# Trottinette_Telemetrie_Circuit.net
KiCad netlist of a schematic drawn in Altium Designer
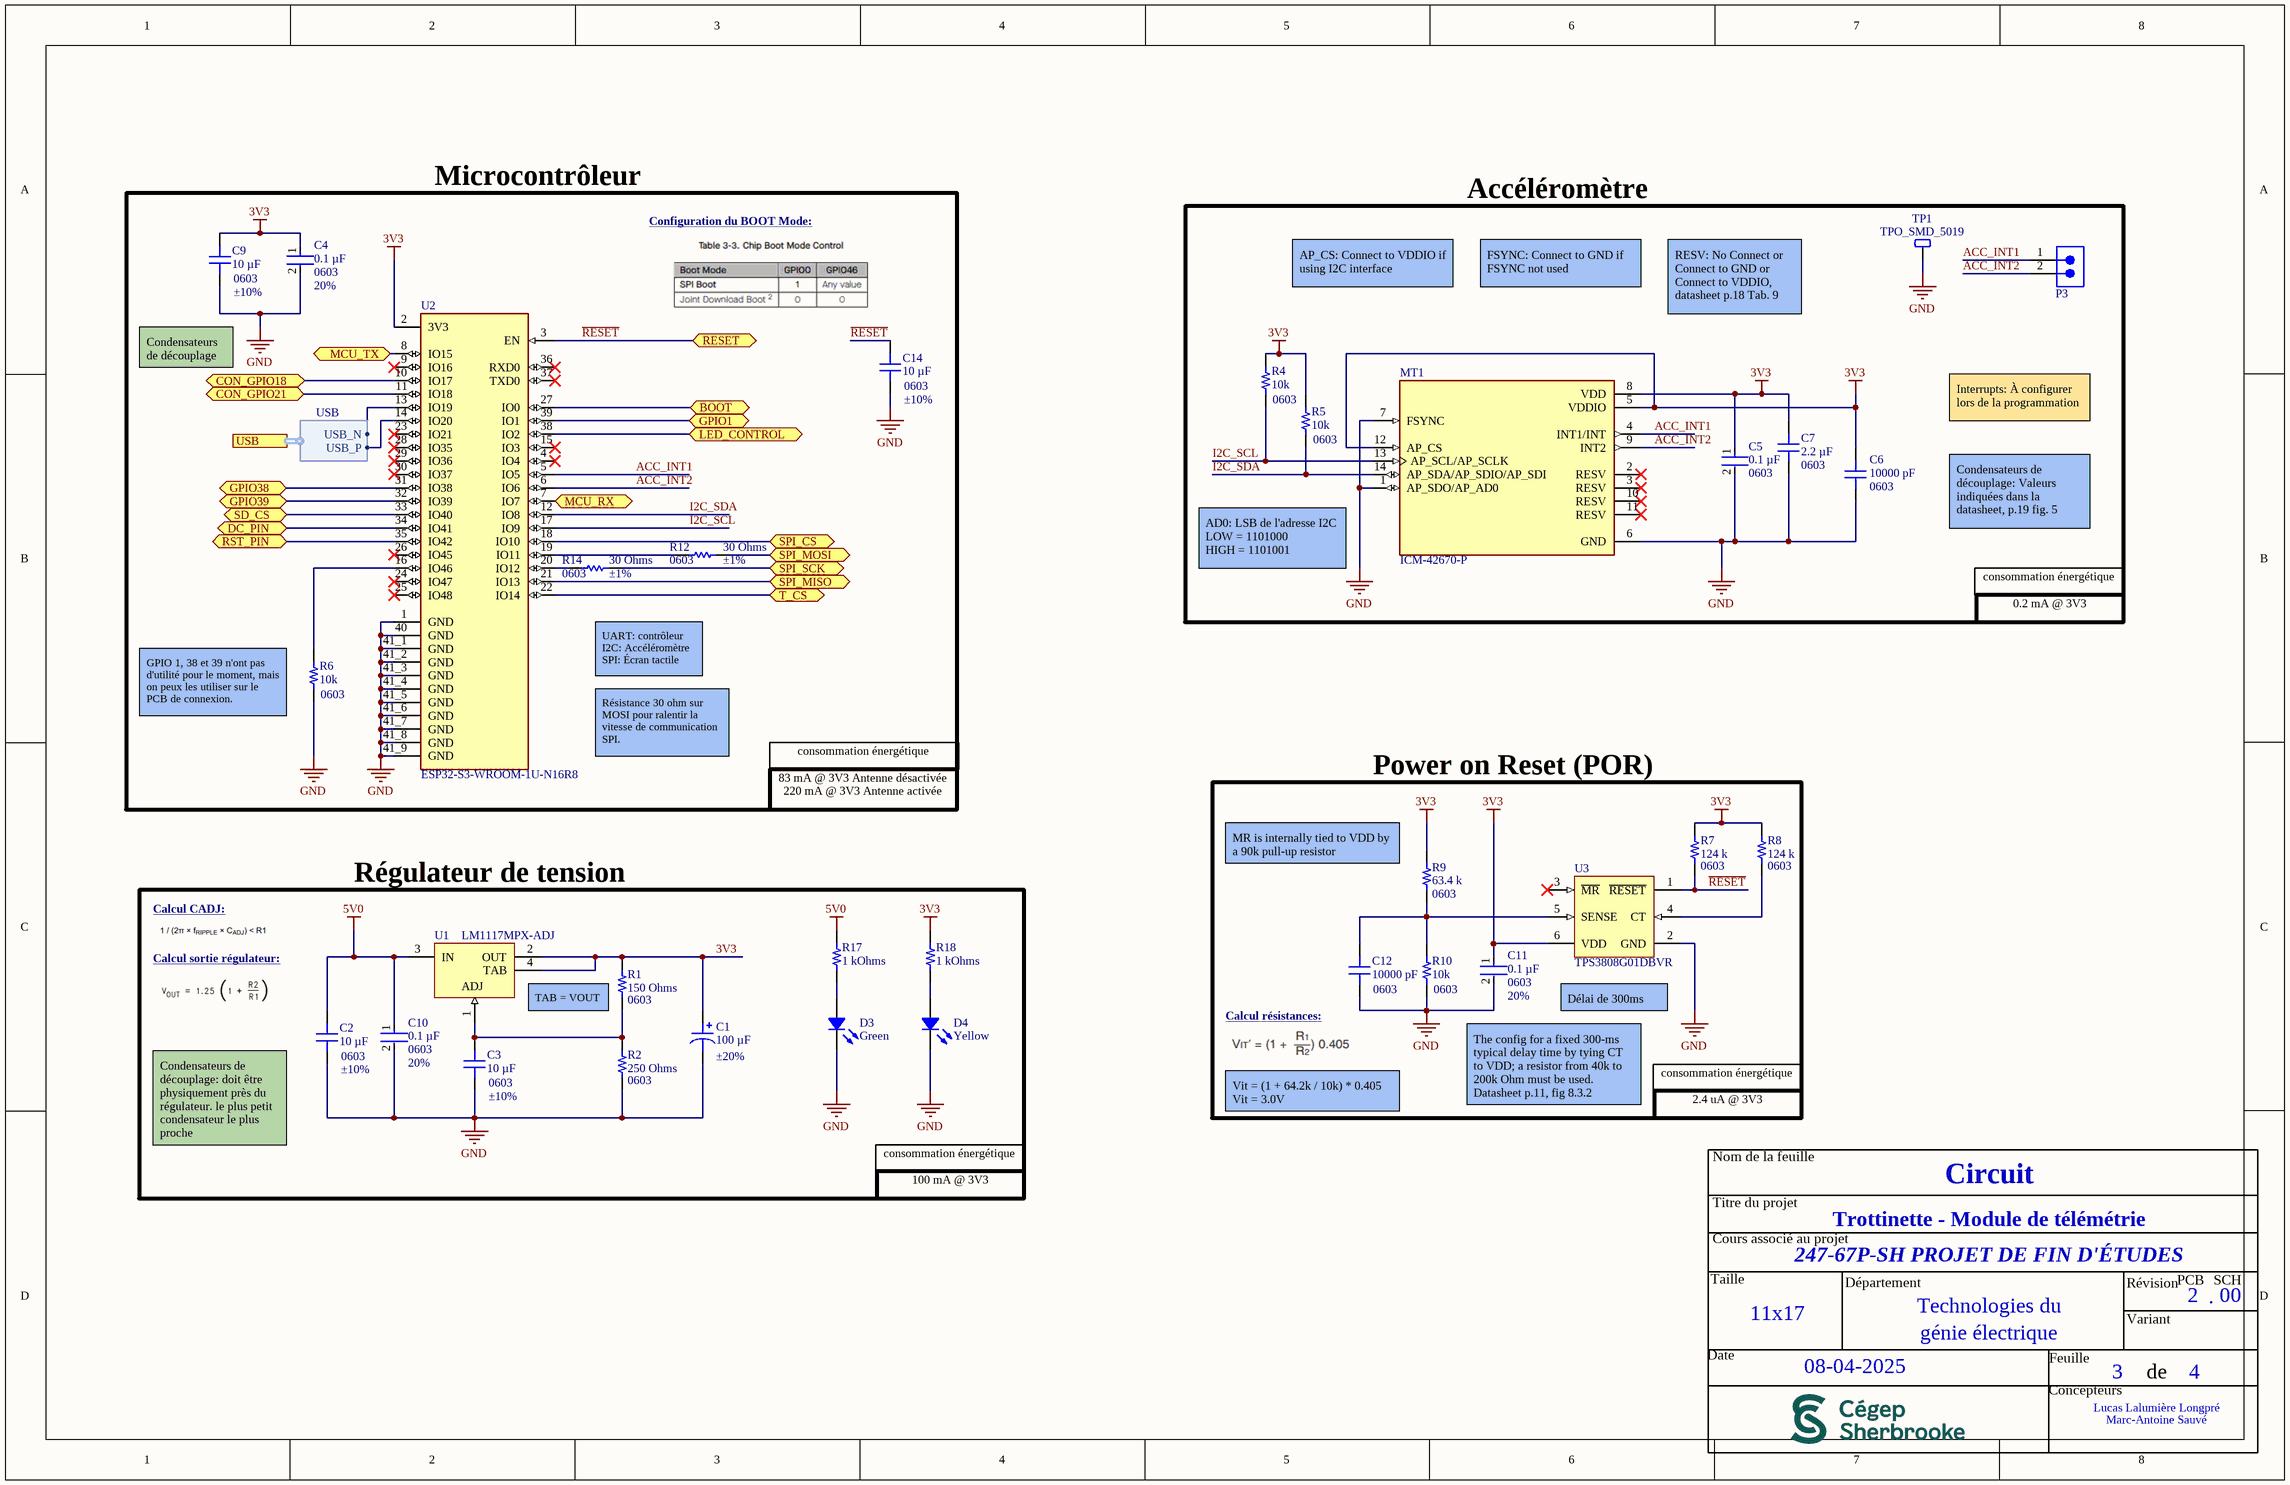
[diagram p0: Trottinette_Telemetrie_Circuit.SchDoc]

(export (version "E")
  (design (tool "Eeschema 10.0.6"))
  (components
    (comp (ref "C1")
      (value "100 µF")
      (footprint "CAP ALSMD 6.6MM H6.1MM")
      (description "CAP ALUM 100UF 20% 10V SMD")
      (fields
        (field (name "PART NUMBER") "10SGV100M6.3X6.1")
        (field (name "MANUFACTURER") "Rubycon")
        (field (name "TOLERANCE") "±20%")
      )
      (libsource (lib "Celestial Altium Library - altium_library") (part "Polarised Capacitor"))
    )
    (comp (ref "C2")
      (value "10 µF")
      (footprint "CAP 0603_1608")
      (description "CAP CER 10UF 10V X5R 0603")
      (fields
        (field (name "PART NUMBER") "GRT188R61A106KE13D")
        (field (name "DEVICE PACKAGE") "0603")
        (field (name "MANUFACTURER") "Murata Electronics")
        (field (name "TOLERANCE") "±10%")
      )
      (libsource (lib "Celestial Altium Library - altium_library") (part "Capacitor"))
    )
    (comp (ref "C3")
      (value "10 µF")
      (footprint "CAP 0603_1608")
      (description "CAP CER 10UF 10V X5R 0603")
      (fields
        (field (name "PART NUMBER") "GRT188R61A106KE13D")
        (field (name "DEVICE PACKAGE") "0603")
        (field (name "MANUFACTURER") "Murata Electronics")
        (field (name "TOLERANCE") "±10%")
      )
      (libsource (lib "Celestial Altium Library - altium_library") (part "Capacitor"))
    )
    (comp (ref "C4")
      (value "0603ZC104MAT2A")
      (footprint "FP-0603-L_1_6_0_15-W_0_81-IPC_B")
      (description "General Purpose Ceramic Capacitor, 0603, 100nF, 20%, X7R, 15%, 10V")
      (fields
        (field (name "CASE CODE (IMPERIAL)") "0603")
        (field (name "TOLERANCE") "20%")
        (field (name "CAPACITANCE") "0.1 µF")
      )
      (libsource (lib "Altium Content Vault") (part "02cd4be3c70576c341d710602a673aa"))
    )
    (comp (ref "C5")
      (value "0603ZC104MAT2A")
      (footprint "FP-0603-L_1_6_0_15-W_0_81-IPC_B")
      (description "General Purpose Ceramic Capacitor, 0603, 100nF, 20%, X7R, 15%, 10V")
      (fields
        (field (name "CASE CODE (IMPERIAL)") "0603")
        (field (name "TOLERANCE") "20%")
        (field (name "CAPACITANCE") "0.1 µF")
      )
      (libsource (lib "Altium Content Vault") (part "02cd4be3c70576c341d710602a673aa"))
    )
    (comp (ref "C6")
      (value "10000 pF")
      (footprint "CAP 0603_1608")
      (description "CAP CER 0603 10NF 16V X7R 10%")
      (fields
        (field (name "PART NUMBER") "C0603C103K4RECAUTO")
        (field (name "MANUFACTURER") "KEMET")
        (field (name "PACKAGE / CASE") "0603")
      )
      (libsource (lib "Celestial Altium Library - altium_library") (part "Capacitor"))
    )
    (comp (ref "C7")
      (value "2.2 µF")
      (footprint "CAP 0603_1608")
      (description "CAP CER 2.2UF 16V Y5V 0603")
      (fields
        (field (name "PART NUMBER") "CC0603ZRY5V7BB225")
        (field (name "MANUFACTURER") "Yageo")
        (field (name "PACKAGE / CASE") "0603")
      )
      (libsource (lib "Celestial Altium Library - altium_library") (part "Capacitor"))
    )
    (comp (ref "C9")
      (value "10 µF")
      (footprint "CAP 0603_1608")
      (description "CAP CER 10UF 10V X5R 0603")
      (fields
        (field (name "PART NUMBER") "GRT188R61A106KE13D")
        (field (name "DEVICE PACKAGE") "0603")
        (field (name "MANUFACTURER") "Murata Electronics")
        (field (name "TOLERANCE") "±10%")
      )
      (libsource (lib "Celestial Altium Library - altium_library") (part "Capacitor"))
    )
    (comp (ref "C10")
      (value "0603ZC104MAT2A")
      (footprint "FP-0603-L_1_6_0_15-W_0_81-IPC_B")
      (description "General Purpose Ceramic Capacitor, 0603, 100nF, 20%, X7R, 15%, 10V")
      (fields
        (field (name "CASE CODE (IMPERIAL)") "0603")
        (field (name "TOLERANCE") "20%")
        (field (name "CAPACITANCE") "0.1 µF")
      )
      (libsource (lib "Altium Content Vault") (part "02cd4be3c70576c341d710602a673aa"))
    )
    (comp (ref "C11")
      (value "0603ZC104MAT2A")
      (footprint "FP-0603-L_1_6_0_15-W_0_81-IPC_B")
      (description "General Purpose Ceramic Capacitor, 0603, 100nF, 20%, X7R, 15%, 10V")
      (fields
        (field (name "CASE CODE (IMPERIAL)") "0603")
        (field (name "TOLERANCE") "20%")
        (field (name "CAPACITANCE") "0.1 µF")
      )
      (libsource (lib "Altium Content Vault") (part "02cd4be3c70576c341d710602a673aa"))
    )
    (comp (ref "C12")
      (value "10000 pF")
      (footprint "CAP 0603_1608")
      (description "CAP CER 10000PF 100V X7R 0603")
      (fields
        (field (name "PART NUMBER") "AC0603KRX7R0BB103")
        (field (name "DEVICE PACKAGE") "0603")
        (field (name "MANUFACTURER") "Yageo")
      )
      (libsource (lib "Celestial Altium Library - altium_library") (part "Capacitor"))
    )
    (comp (ref "C14")
      (value "10 µF")
      (footprint "CAP 0603_1608")
      (description "CAP CER 10UF 10V X5R 0603")
      (fields
        (field (name "PART NUMBER") "GRT188R61A106KE13D")
        (field (name "DEVICE PACKAGE") "0603")
        (field (name "MANUFACTURER") "Murata Electronics")
        (field (name "TOLERANCE") "±10%")
      )
      (libsource (lib "Celestial Altium Library - altium_library") (part "Capacitor"))
    )
    (comp (ref "D3")
      (value "Green")
      (footprint "LED 0603_1608 GREEN")
      (description "LED GREEN 0603 SMD")
      (fields (field (name "PART NUMBER") "5973316507F") (field (name "MANUFACTURER") "Dialight"))
      (libsource (lib "Celestial Altium Library - altium_library") (part "LED"))
    )
    (comp (ref "D4")
      (value "Yellow")
      (footprint "LED 0603_1608 YELLOW")
      (description "LED YELLOW 0603 SMD")
      (fields (field (name "PART NUMBER") "5990040007F") (field (name "MANUFACTURER") "Dialight"))
      (libsource (lib "Celestial Altium Library - altium_library") (part "LED"))
    )
    (comp (ref "MT1")
      (value "ICM-42670-P")
      (footprint "XDCR_ICM-42670-P")
      (libsource (lib "ICM-42670-P") (part "ICM-42670-P"))
    )
    (comp (ref "P3")
      (value "61300211121")
      (footprint "61300211121")
      (description "WR-PHD Pin Header, THT, Vertical, pitch 2.54mm, 1 Row, 2P")
      (fields (field (name "MANUFACTURER") "Wurth Elektronik"))
      (libsource (lib "Altium_WR-PHD_rev24a") (part "61300211121"))
    )
    (comp (ref "R1")
      (value "150 Ohms")
      (footprint "RES 0603_1608")
      (description "RES 150 OHM 1% 1/10W 0603")
      (fields
        (field (name "PART NUMBER") "RMCF0603FT150R")
        (field (name "MANUFACTURER") "Stackpole Electronics Inc")
        (field (name "SUPPLIER DEVICE PACKAGE") "0603")
      )
      (libsource (lib "Celestial Altium Library - altium_library") (part "Resistor"))
    )
    (comp (ref "R2")
      (value "250 Ohms")
      (footprint "RES 0603_1608")
      (description "RES 250 OHM 5% 1/8W 0603")
      (fields
        (field (name "PART NUMBER") "CH0603-250RJNTA")
        (field (name "MANUFACTURER") "Vishay Sfernice")
        (field (name "SUPPLIER DEVICE PACKAGE") "0603")
      )
      (libsource (lib "Celestial Altium Library - altium_library") (part "Resistor"))
    )
    (comp (ref "R4")
      (value "10k")
      (footprint "RES 0603_1608")
      (description "RES 10K OHM 0.1% 1/16W 0603")
      (fields
        (field (name "PART NUMBER") "RNCS0603BKE10K0")
        (field (name "MANUFACTURER") "Stackpole Electronics Inc")
        (field (name "SUPPLIER DEVICE PACKAGE") "0603")
      )
      (libsource (lib "Celestial Altium Library - altium_library") (part "Resistor"))
    )
    (comp (ref "R5")
      (value "10k")
      (footprint "RES 0603_1608")
      (description "RES 10K OHM 0.1% 1/16W 0603")
      (fields
        (field (name "PART NUMBER") "RNCS0603BKE10K0")
        (field (name "MANUFACTURER") "Stackpole Electronics Inc")
        (field (name "SUPPLIER DEVICE PACKAGE") "0603")
      )
      (libsource (lib "Celestial Altium Library - altium_library") (part "Resistor"))
    )
    (comp (ref "R6")
      (value "10k")
      (footprint "RES 0603_1608")
      (description "RES 10K OHM 0.1% 1/16W 0603")
      (fields
        (field (name "PART NUMBER") "RNCS0603BKE10K0")
        (field (name "MANUFACTURER") "Stackpole Electronics Inc")
        (field (name "SUPPLIER DEVICE PACKAGE") "0603")
      )
      (libsource (lib "Celestial Altium Library - altium_library") (part "Resistor"))
    )
    (comp (ref "R7")
      (value "124 k")
      (footprint "RES 0603_1608")
      (description "RES 124K OHM 1% 1/10W 0603")
      (fields
        (field (name "PART NUMBER") "RMCF0603FT124K")
        (field (name "MANUFACTURER") "Stackpole Electronics Inc")
        (field (name "SUPPLIER DEVICE PACKAGE") "0603")
      )
      (libsource (lib "Celestial Altium Library - altium_library") (part "Resistor"))
    )
    (comp (ref "R8")
      (value "124 k")
      (footprint "RES 0603_1608")
      (description "RES 124K OHM 1% 1/10W 0603")
      (fields
        (field (name "PART NUMBER") "RMCF0603FT124K")
        (field (name "MANUFACTURER") "Stackpole Electronics Inc")
        (field (name "SUPPLIER DEVICE PACKAGE") "0603")
      )
      (libsource (lib "Celestial Altium Library - altium_library") (part "Resistor"))
    )
    (comp (ref "R9")
      (value "63.4 k")
      (footprint "RES 0603_1608")
      (description "RES 63.4K OHM 1% 1/10W 0603")
      (fields
        (field (name "PART NUMBER") "RMCF0603FT63K4")
        (field (name "MANUFACTURER") "Stackpole Electronics Inc")
        (field (name "SUPPLIER DEVICE PACKAGE") "0603")
      )
      (libsource (lib "Celestial Altium Library - altium_library") (part "Resistor"))
    )
    (comp (ref "R10")
      (value "10k")
      (footprint "RES 0603_1608")
      (description "RES 10K OHM 0.1% 1/16W 0603")
      (fields
        (field (name "PART NUMBER") "RNCS0603BKE10K0")
        (field (name "MANUFACTURER") "Stackpole Electronics Inc")
        (field (name "SUPPLIER DEVICE PACKAGE") "0603")
      )
      (libsource (lib "Celestial Altium Library - altium_library") (part "Resistor"))
    )
    (comp (ref "R12")
      (value "ERJ3EKF30R0V")
      (footprint "RESC1608X55X30LL15T15")
      (fields (field (name "MANUFACTURER") "Panasonic"))
      (libsource (lib "Altium Content Vault") (part "RES"))
    )
    (comp (ref "R14")
      (value "ERJ3EKF30R0V")
      (footprint "RESC1608X55X30LL15T15")
      (fields (field (name "MANUFACTURER") "Panasonic"))
      (libsource (lib "Altium Content Vault") (part "RES"))
    )
    (comp (ref "R17")
      (value "1 kOhms")
      (footprint "RES 0603_1608")
      (description "RES SMD 1K OHM 0.1% 1/16W 0603")
      (fields
        (field (name "PART NUMBER") "CPF0603B1K0E")
        (field (name "MANUFACTURER") "TE Connectivity Passive Product")
      )
      (libsource (lib "Celestial Altium Library - altium_library") (part "Resistor"))
    )
    (comp (ref "R18")
      (value "1 kOhms")
      (footprint "RES 0603_1608")
      (description "RES SMD 1K OHM 0.1% 1/16W 0603")
      (fields
        (field (name "PART NUMBER") "CPF0603B1K0E")
        (field (name "MANUFACTURER") "TE Connectivity Passive Product")
      )
      (libsource (lib "Celestial Altium Library - altium_library") (part "Resistor"))
    )
    (comp (ref "TP1")
      (value "TPO_SMD_5019")
      (footprint "TPO_SMD_5019")
      (description "TPO - PC TEST POINT MINI - SMD")
      (fields (field (name "SOURCE") "CEGEP_SHERBROOKE_TGE_LIBRARY.SchLib"))
      (libsource (lib "Cegep de Sherbrooke") (part "TPO_SMD_5019"))
    )
    (comp (ref "U1")
      (value "LM1117MPX-ADJ")
      (footprint "MP04A_N")
      (description "800mA Low-Dropout Linear Regulator, 4-pin SOT-223")
      (fields (field (name "MANUFACTURER") "National Semiconductor"))
      (libsource (lib "Altium Content Vault") (part "PM-REG-LM1086ADJ-SOT4"))
    )
    (comp (ref "U2")
      (value "ESP32-S3-WROOM-1U-N16R8")
      (footprint "XCVR_ESP32-S3-WROOM-1U-N16R8")
      (fields (field (name "MF") "Espressif Systems"))
      (libsource (lib "ESP32-S3-WROOM-1U-N16R8") (part "ESP32-S3-WROOM-1U-N16R8"))
    )
    (comp (ref "U3")
      (value "TPS3808G01DBVR")
      (footprint "DBV0006A_L")
      (fields (field (name "MANUFACTURER") "Texas Instruments"))
      (libsource (lib "Altium Content Vault") (part "TI-TPS3808G01DBV6"))
    )
  )
  (nets
    (net (code "2") (name "/ACC_INT1") (class "Default")
      (node (ref "MT1") (pin "4") (pinfunction "INT1/INT_4") (pintype "output"))
      (node (ref "P3") (pin "1") (pinfunction "1_1") (pintype "passive"))
      (node (ref "U2") (pin "5") (pinfunction "IO5_5") (pintype "bidirectional"))
    )
    (net (code "3") (name "/ACC_INT2") (class "Default")
      (node (ref "MT1") (pin "9") (pinfunction "INT2_9") (pintype "output"))
      (node (ref "P3") (pin "2") (pinfunction "2_2") (pintype "passive"))
      (node (ref "U2") (pin "6") (pinfunction "IO6_6") (pintype "bidirectional"))
    )
    (net (code "4") (name "/BOOT") (class "Default")
      (node (ref "U2") (pin "27") (pinfunction "IO0_27") (pintype "bidirectional"))
    )
    (net (code "5") (name "/CON_GPIO18") (class "Default")
      (node (ref "U2") (pin "10") (pinfunction "IO17_10") (pintype "bidirectional"))
    )
    (net (code "6") (name "/CON_GPIO21") (class "Default")
      (node (ref "U2") (pin "11") (pinfunction "IO18_11") (pintype "bidirectional"))
    )
    (net (code "7") (name "/DC_PIN") (class "Default")
      (node (ref "U2") (pin "34") (pinfunction "IO41_34") (pintype "bidirectional"))
    )
    (net (code "8") (name "/GPIO1") (class "Default")
      (node (ref "U2") (pin "39") (pinfunction "IO1_39") (pintype "bidirectional"))
    )
    (net (code "9") (name "/GPIO38") (class "Default")
      (node (ref "U2") (pin "31") (pinfunction "IO38_31") (pintype "bidirectional"))
    )
    (net (code "10") (name "/GPIO39") (class "Default")
      (node (ref "U2") (pin "32") (pinfunction "IO39_32") (pintype "bidirectional"))
    )
    (net (code "11") (name "/I2C_SCL") (class "Default")
      (node (ref "MT1") (pin "13") (pinfunction "AP_SCL/AP_SCLK_13") (pintype "input"))
      (node (ref "R4") (pin "1") (pinfunction "1_1") (pintype "passive"))
      (node (ref "U2") (pin "17") (pinfunction "IO9_17") (pintype "bidirectional"))
    )
    (net (code "12") (name "/I2C_SDA") (class "Default")
      (node (ref "MT1") (pin "14") (pinfunction "AP_SDA/AP_SDIO/AP_SDI_14") (pintype "bidirectional"))
      (node (ref "R5") (pin "1") (pinfunction "1_1") (pintype "passive"))
      (node (ref "U2") (pin "12") (pinfunction "IO8_12") (pintype "bidirectional"))
    )
    (net (code "13") (name "/LED_CONTROL") (class "Default")
      (node (ref "U2") (pin "38") (pinfunction "IO2_38") (pintype "bidirectional"))
    )
    (net (code "14") (name "/MCU_RX") (class "Default")
      (node (ref "U2") (pin "7") (pinfunction "IO7_7") (pintype "bidirectional"))
    )
    (net (code "15") (name "/MCU_TX") (class "Default")
      (node (ref "U2") (pin "8") (pinfunction "IO15_8") (pintype "bidirectional"))
    )
    (net (code "16") (name "/RESET") (class "Default")
      (node (ref "C14") (pin "2") (pinfunction "2_2") (pintype "passive"))
      (node (ref "R7") (pin "1") (pinfunction "1_1") (pintype "passive"))
      (node (ref "U2") (pin "3") (pinfunction "EN_3") (pintype "input"))
      (node (ref "U3") (pin "1") (pinfunction "~{RESET}_1") (pintype "tri_state"))
    )
    (net (code "17") (name "/RST_PIN") (class "Default")
      (node (ref "U2") (pin "35") (pinfunction "IO42_35") (pintype "bidirectional"))
    )
    (net (code "18") (name "/SD_CS") (class "Default")
      (node (ref "U2") (pin "33") (pinfunction "IO40_33") (pintype "bidirectional"))
    )
    (net (code "19") (name "/SPI_CS") (class "Default")
      (node (ref "U2") (pin "18") (pinfunction "IO10_18") (pintype "bidirectional"))
    )
    (net (code "20") (name "/SPI_MISO") (class "Default")
      (node (ref "U2") (pin "21") (pinfunction "IO13_21") (pintype "bidirectional"))
    )
    (net (code "21") (name "/SPI_MOSI") (class "Default")
      (node (ref "R12") (pin "2") (pinfunction "2_2") (pintype "passive"))
    )
    (net (code "22") (name "/SPI_SCK") (class "Default")
      (node (ref "R14") (pin "2") (pinfunction "2_2") (pintype "passive"))
    )
    (net (code "23") (name "/T_CS") (class "Default")
      (node (ref "U2") (pin "22") (pinfunction "IO14_22") (pintype "bidirectional"))
    )
    (net (code "24") (name "/USB_N") (class "Default")
      (node (ref "U2") (pin "13") (pinfunction "IO19_13") (pintype "bidirectional"))
    )
    (net (code "25") (name "/USB_P") (class "Default")
      (node (ref "U2") (pin "14") (pinfunction "IO20_14") (pintype "bidirectional"))
    )
    (net (code "27") (name "3V3") (class "Default")
      (node (ref "C1") (pin "1") (pinfunction "1_1") (pintype "passive"))
      (node (ref "C11") (pin "1") (pinfunction "1_1") (pintype "passive"))
      (node (ref "C4") (pin "1") (pinfunction "1_1") (pintype "passive"))
      (node (ref "C5") (pin "1") (pinfunction "1_1") (pintype "passive"))
      (node (ref "C6") (pin "2") (pinfunction "2_2") (pintype "passive"))
      (node (ref "C7") (pin "2") (pinfunction "2_2") (pintype "passive"))
      (node (ref "C9") (pin "2") (pinfunction "2_2") (pintype "passive"))
      (node (ref "MT1") (pin "12") (pinfunction "AP_CS_12") (pintype "input"))
      (node (ref "MT1") (pin "5") (pinfunction "VDDIO_5") (pintype "power_in"))
      (node (ref "MT1") (pin "8") (pinfunction "VDD_8") (pintype "power_in"))
      (node (ref "R1") (pin "2") (pinfunction "2_2") (pintype "passive"))
      (node (ref "R18") (pin "1") (pinfunction "1_1") (pintype "passive"))
      (node (ref "R4") (pin "2") (pinfunction "2_2") (pintype "passive"))
      (node (ref "R5") (pin "2") (pinfunction "2_2") (pintype "passive"))
      (node (ref "R7") (pin "2") (pinfunction "2_2") (pintype "passive"))
      (node (ref "R8") (pin "2") (pinfunction "2_2") (pintype "passive"))
      (node (ref "R9") (pin "2") (pinfunction "2_2") (pintype "passive"))
      (node (ref "U1") (pin "2") (pinfunction "OUT_2") (pintype "power_in"))
      (node (ref "U1") (pin "4") (pinfunction "TAB_4") (pintype "power_in"))
      (node (ref "U2") (pin "2") (pinfunction "3V3_2") (pintype "power_in"))
      (node (ref "U3") (pin "6") (pinfunction "VDD_6") (pintype "power_in"))
    )
    (net (code "28") (name "5V0") (class "Default")
      (node (ref "C10") (pin "1") (pinfunction "1_1") (pintype "passive"))
      (node (ref "C2") (pin "2") (pinfunction "2_2") (pintype "passive"))
      (node (ref "R17") (pin "1") (pinfunction "1_1") (pintype "passive"))
      (node (ref "U1") (pin "3") (pinfunction "IN_3") (pintype "power_in"))
    )
    (net (code "29") (name "GND") (class "Default")
      (node (ref "C1") (pin "2") (pinfunction "2_2") (pintype "passive"))
      (node (ref "C10") (pin "2") (pinfunction "2_2") (pintype "passive"))
      (node (ref "C11") (pin "2") (pinfunction "2_2") (pintype "passive"))
      (node (ref "C12") (pin "1") (pinfunction "1_1") (pintype "passive"))
      (node (ref "C14") (pin "1") (pinfunction "1_1") (pintype "passive"))
      (node (ref "C2") (pin "1") (pinfunction "1_1") (pintype "passive"))
      (node (ref "C3") (pin "1") (pinfunction "1_1") (pintype "passive"))
      (node (ref "C4") (pin "2") (pinfunction "2_2") (pintype "passive"))
      (node (ref "C5") (pin "2") (pinfunction "2_2") (pintype "passive"))
      (node (ref "C6") (pin "1") (pinfunction "1_1") (pintype "passive"))
      (node (ref "C7") (pin "1") (pinfunction "1_1") (pintype "passive"))
      (node (ref "C9") (pin "1") (pinfunction "1_1") (pintype "passive"))
      (node (ref "D3") (pin "2") (pinfunction "2_2") (pintype "passive"))
      (node (ref "D4") (pin "2") (pinfunction "2_2") (pintype "passive"))
      (node (ref "MT1") (pin "1") (pinfunction "AP_SDO/AP_AD0_1") (pintype "bidirectional"))
      (node (ref "MT1") (pin "6") (pinfunction "GND_6") (pintype "power_in"))
      (node (ref "MT1") (pin "7") (pinfunction "FSYNC_7") (pintype "input"))
      (node (ref "R10") (pin "1") (pinfunction "1_1") (pintype "passive"))
      (node (ref "R2") (pin "1") (pinfunction "1_1") (pintype "passive"))
      (node (ref "R6") (pin "1") (pinfunction "1_1") (pintype "passive"))
      (node (ref "TP1") (pin "1") (pinfunction "1_1") (pintype "passive"))
      (node (ref "U2") (pin "1") (pinfunction "GND_1") (pintype "power_in"))
      (node (ref "U2") (pin "40") (pinfunction "GND_40") (pintype "power_in"))
      (node (ref "U2") (pin "41_1") (pinfunction "GND_41_1") (pintype "power_in"))
      (node (ref "U2") (pin "41_2") (pinfunction "GND_41_2") (pintype "power_in"))
      (node (ref "U2") (pin "41_3") (pinfunction "GND_41_3") (pintype "power_in"))
      (node (ref "U2") (pin "41_4") (pinfunction "GND_41_4") (pintype "power_in"))
      (node (ref "U2") (pin "41_5") (pinfunction "GND_41_5") (pintype "power_in"))
      (node (ref "U2") (pin "41_6") (pinfunction "GND_41_6") (pintype "power_in"))
      (node (ref "U2") (pin "41_7") (pinfunction "GND_41_7") (pintype "power_in"))
      (node (ref "U2") (pin "41_8") (pinfunction "GND_41_8") (pintype "power_in"))
      (node (ref "U2") (pin "41_9") (pinfunction "GND_41_9") (pintype "power_in"))
      (node (ref "U3") (pin "2") (pinfunction "GND_2") (pintype "power_in"))
    )
    (net (code "30") (name "Net-(D3-Pad1)") (class "Default")
      (node (ref "D3") (pin "1") (pinfunction "1_1") (pintype "passive"))
      (node (ref "R17") (pin "2") (pinfunction "2_2") (pintype "passive"))
    )
    (net (code "31") (name "Net-(D4-Pad1)") (class "Default")
      (node (ref "D4") (pin "1") (pinfunction "1_1") (pintype "passive"))
      (node (ref "R18") (pin "2") (pinfunction "2_2") (pintype "passive"))
    )
    (net (code "32") (name "Net-(U1-ADJ)") (class "Default")
      (node (ref "C3") (pin "2") (pinfunction "2_2") (pintype "passive"))
      (node (ref "R1") (pin "1") (pinfunction "1_1") (pintype "passive"))
      (node (ref "R2") (pin "2") (pinfunction "2_2") (pintype "passive"))
      (node (ref "U1") (pin "1") (pinfunction "ADJ_1") (pintype "input"))
    )
    (net (code "33") (name "Net-(U2-IO11)") (class "Default")
      (node (ref "R12") (pin "1") (pinfunction "1_1") (pintype "passive"))
      (node (ref "U2") (pin "19") (pinfunction "IO11_19") (pintype "bidirectional"))
    )
    (net (code "34") (name "Net-(U2-IO12)") (class "Default")
      (node (ref "R14") (pin "1") (pinfunction "1_1") (pintype "passive"))
      (node (ref "U2") (pin "20") (pinfunction "IO12_20") (pintype "bidirectional"))
    )
    (net (code "35") (name "Net-(U2-IO46)") (class "Default")
      (node (ref "R6") (pin "2") (pinfunction "2_2") (pintype "passive"))
      (node (ref "U2") (pin "16") (pinfunction "IO46_16") (pintype "bidirectional"))
    )
    (net (code "36") (name "Net-(U3-CT)") (class "Default")
      (node (ref "R8") (pin "1") (pinfunction "1_1") (pintype "passive"))
      (node (ref "U3") (pin "4") (pinfunction "CT_4") (pintype "input"))
    )
    (net (code "37") (name "Net-(U3-SENSE)") (class "Default")
      (node (ref "C12") (pin "2") (pinfunction "2_2") (pintype "passive"))
      (node (ref "R10") (pin "2") (pinfunction "2_2") (pintype "passive"))
      (node (ref "R9") (pin "1") (pinfunction "1_1") (pintype "passive"))
      (node (ref "U3") (pin "5") (pinfunction "SENSE_5") (pintype "input"))
    )
    (net (code "38") (name "unconnected-(MT1-RESV-Pad2)") (class "Default")
      (node (ref "MT1") (pin "2") (pinfunction "RESV_2") (pintype "passive+no_connect"))
    )
    (net (code "39") (name "unconnected-(MT1-RESV-Pad3)") (class "Default")
      (node (ref "MT1") (pin "3") (pinfunction "RESV_3") (pintype "passive+no_connect"))
    )
    (net (code "40") (name "unconnected-(MT1-RESV-Pad10)") (class "Default")
      (node (ref "MT1") (pin "10") (pinfunction "RESV_10") (pintype "passive+no_connect"))
    )
    (net (code "41") (name "unconnected-(MT1-RESV-Pad11)") (class "Default")
      (node (ref "MT1") (pin "11") (pinfunction "RESV_11") (pintype "passive+no_connect"))
    )
    (net (code "42") (name "unconnected-(U2-IO3-Pad15)") (class "Default")
      (node (ref "U2") (pin "15") (pinfunction "IO3_15") (pintype "bidirectional+no_connect"))
    )
    (net (code "43") (name "unconnected-(U2-IO4-Pad4)") (class "Default")
      (node (ref "U2") (pin "4") (pinfunction "IO4_4") (pintype "bidirectional+no_connect"))
    )
    (net (code "44") (name "unconnected-(U2-IO16-Pad9)") (class "Default")
      (node (ref "U2") (pin "9") (pinfunction "IO16_9") (pintype "bidirectional+no_connect"))
    )
    (net (code "45") (name "unconnected-(U2-IO21-Pad23)") (class "Default")
      (node (ref "U2") (pin "23") (pinfunction "IO21_23") (pintype "bidirectional+no_connect"))
    )
    (net (code "46") (name "unconnected-(U2-IO35-Pad28)") (class "Default")
      (node (ref "U2") (pin "28") (pinfunction "IO35_28") (pintype "bidirectional+no_connect"))
    )
    (net (code "47") (name "unconnected-(U2-IO36-Pad29)") (class "Default")
      (node (ref "U2") (pin "29") (pinfunction "IO36_29") (pintype "bidirectional+no_connect"))
    )
    (net (code "48") (name "unconnected-(U2-IO37-Pad30)") (class "Default")
      (node (ref "U2") (pin "30") (pinfunction "IO37_30") (pintype "bidirectional+no_connect"))
    )
    (net (code "49") (name "unconnected-(U2-IO45-Pad26)") (class "Default")
      (node (ref "U2") (pin "26") (pinfunction "IO45_26") (pintype "bidirectional+no_connect"))
    )
    (net (code "50") (name "unconnected-(U2-IO47-Pad24)") (class "Default")
      (node (ref "U2") (pin "24") (pinfunction "IO47_24") (pintype "bidirectional+no_connect"))
    )
    (net (code "51") (name "unconnected-(U2-IO48-Pad25)") (class "Default")
      (node (ref "U2") (pin "25") (pinfunction "IO48_25") (pintype "bidirectional+no_connect"))
    )
    (net (code "52") (name "unconnected-(U2-RXD0-Pad36)") (class "Default")
      (node (ref "U2") (pin "36") (pinfunction "RXD0_36") (pintype "bidirectional+no_connect"))
    )
    (net (code "53") (name "unconnected-(U2-TXD0-Pad37)") (class "Default")
      (node (ref "U2") (pin "37") (pinfunction "TXD0_37") (pintype "bidirectional+no_connect"))
    )
    (net (code "54") (name "unconnected-(U3-~{MR}-Pad3)") (class "Default")
      (node (ref "U3") (pin "3") (pinfunction "~{MR}_3") (pintype "input+no_connect"))
    )
  )
)
